# Telemetry_868Mhz.net
KiCad netlist of a schematic drawn in Altium Designer
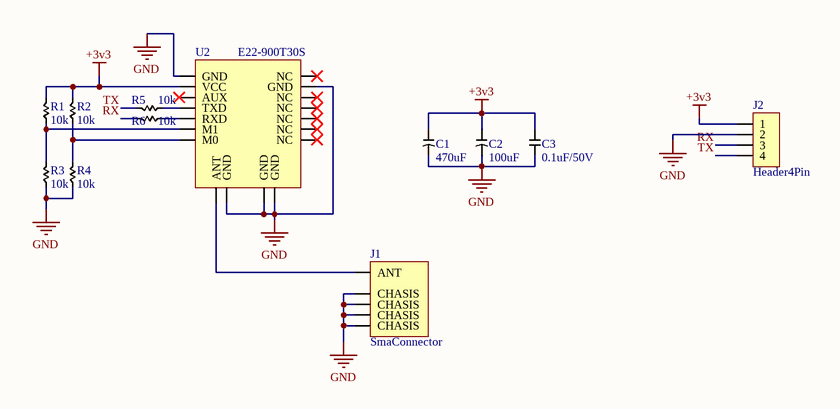
[diagram p0: Telemetry_868Mhz.SchDoc]

(export (version "E")
  (design (tool "Eeschema 10.0.6"))
  (components
    (comp (ref "C1")
      (value "470uF")
      (footprint "PKLH-016V471MG125-T/A5.0")
      (description "CAP.EL.470uF 16V 10x12.5 5MM 105C L.ESR 3000H TB K")
      (libsource (lib "Roket_Library") (part "PKLH-016V471MG125-T/A5.0"))
    )
    (comp (ref "C2")
      (value "100uF")
      (footprint "PKRM-035V101ME110-T/A5.0")
      (description "CAP.EL.100uF 50V 10x10 105C TH")
      (libsource (lib "Roket_Library") (part "PKRM-035V101ME110-T/A5.0"))
    )
    (comp (ref "C3")
      (value "0.1uF/50V")
      (footprint "Cap_0805")
      (description "MLCC (2012) 0805 100nF 50VDC ±5% X7R")
      (libsource (lib "Roket_Library") (part "CL21B104JBCNNNC"))
    )
    (comp (ref "J1")
      (value "SmaConnector")
      (footprint "RightAngled_SMA_Connector")
      (description "RP-SMA Connector Receptacle, Male Pin 50Ohm Through Hole, Right Angle Solder")
      (libsource (lib "Roket_Library") (part "L-KLS1-SMA002-B"))
    )
    (comp (ref "J2")
      (value "Header4Pin")
      (footprint "Header_4pin_Female")
      (description "PIN HEADER 4PIN(1x4) 2.54mm THT V/T")
      (libsource (lib "Roket_Library") (part "Header_4Pin"))
    )
    (comp (ref "R1")
      (value "10k")
      (footprint "RES_0805")
      (description "RES.(2012) 0805 10K Ohms 5% 1/8W-S 100PPM")
      (libsource (lib "Roket_Library") (part "0805S8J0103T5E"))
    )
    (comp (ref "R2")
      (value "10k")
      (footprint "RES_0805")
      (description "RES.(2012) 0805 10K Ohms 5% 1/8W-S 100PPM")
      (libsource (lib "Roket_Library") (part "0805S8J0103T5E"))
    )
    (comp (ref "R3")
      (value "10k")
      (footprint "RES_0805")
      (description "RES.(2012) 0805 10K Ohms 5% 1/8W-S 100PPM")
      (libsource (lib "Roket_Library") (part "0805S8J0103T5E"))
    )
    (comp (ref "R4")
      (value "10k")
      (footprint "RES_0805")
      (description "RES.(2012) 0805 10K Ohms 5% 1/8W-S 100PPM")
      (libsource (lib "Roket_Library") (part "0805S8J0103T5E"))
    )
    (comp (ref "R5")
      (value "10k")
      (footprint "RES_0805")
      (description "RES.(2012) 0805 10K Ohms 5% 1/8W-S 100PPM")
      (libsource (lib "Roket_Library") (part "0805S8J0103T5E"))
    )
    (comp (ref "R6")
      (value "10k")
      (footprint "RES_0805")
      (description "RES.(2012) 0805 10K Ohms 5% 1/8W-S 100PPM")
      (libsource (lib "Roket_Library") (part "0805S8J0103T5E"))
    )
    (comp (ref "U2")
      (value "E22-900T30S")
      (footprint "E22-900T30S")
      (description "LoRa, 868MHz 1W SMD long range, 5V Supply,RF Transmission 30 dBm, 10 k")
      (libsource (lib "Roket_Library") (part "E22-900T30S"))
    )
  )
  (nets
    (net (code "1") (name "+3v3") (class "Default")
      (node (ref "C1") (pin "1") (pinfunction "1_1") (pintype "passive"))
      (node (ref "C2") (pin "1") (pinfunction "1_1") (pintype "passive"))
      (node (ref "C3") (pin "1") (pinfunction "1_1") (pintype "passive"))
      (node (ref "J2") (pin "1") (pinfunction "1_1") (pintype "passive"))
      (node (ref "R1") (pin "2") (pinfunction "2_2") (pintype "passive"))
      (node (ref "R2") (pin "2") (pinfunction "2_2") (pintype "passive"))
      (node (ref "U2") (pin "6") (pinfunction "VCC_6") (pintype "passive"))
    )
    (net (code "2") (name "/RX") (class "Default")
      (node (ref "J2") (pin "3") (pinfunction "3_3") (pintype "passive"))
      (node (ref "R6") (pin "2") (pinfunction "2_2") (pintype "passive"))
    )
    (net (code "3") (name "/TX") (class "Default")
      (node (ref "J2") (pin "4") (pinfunction "4_4") (pintype "passive"))
      (node (ref "R5") (pin "2") (pinfunction "2_2") (pintype "passive"))
    )
    (net (code "4") (name "GND") (class "Default")
      (node (ref "C1") (pin "2") (pinfunction "2_2") (pintype "passive"))
      (node (ref "C2") (pin "2") (pinfunction "2_2") (pintype "passive"))
      (node (ref "C3") (pin "2") (pinfunction "2_2") (pintype "passive"))
      (node (ref "J1") (pin "2") (pinfunction "CHASIS_2") (pintype "passive"))
      (node (ref "J1") (pin "3") (pinfunction "CHASIS_3") (pintype "passive"))
      (node (ref "J1") (pin "4") (pinfunction "CHASIS_4") (pintype "passive"))
      (node (ref "J1") (pin "5") (pinfunction "CHASIS_5") (pintype "passive"))
      (node (ref "J2") (pin "2") (pinfunction "2_2") (pintype "passive"))
      (node (ref "R3") (pin "1") (pinfunction "1_1") (pintype "passive"))
      (node (ref "R4") (pin "1") (pinfunction "1_1") (pintype "passive"))
      (node (ref "U2") (pin "15") (pinfunction "GND_15") (pintype "passive"))
      (node (ref "U2") (pin "16") (pinfunction "GND_16") (pintype "passive"))
      (node (ref "U2") (pin "17") (pinfunction "GND_17") (pintype "passive"))
      (node (ref "U2") (pin "7") (pinfunction "GND_7") (pintype "passive"))
      (node (ref "U2") (pin "9") (pinfunction "GND_9") (pintype "passive"))
    )
    (net (code "5") (name "Net-(J1-ANT)") (class "Default")
      (node (ref "J1") (pin "1") (pinfunction "ANT_1") (pintype "passive"))
      (node (ref "U2") (pin "18") (pinfunction "ANT_18") (pintype "passive"))
    )
    (net (code "6") (name "Net-(U2-M0)") (class "Default")
      (node (ref "R2") (pin "1") (pinfunction "1_1") (pintype "passive"))
      (node (ref "R4") (pin "2") (pinfunction "2_2") (pintype "passive"))
      (node (ref "U2") (pin "1") (pinfunction "M0_1") (pintype "passive"))
    )
    (net (code "7") (name "Net-(U2-M1)") (class "Default")
      (node (ref "R1") (pin "1") (pinfunction "1_1") (pintype "passive"))
      (node (ref "R3") (pin "2") (pinfunction "2_2") (pintype "passive"))
      (node (ref "U2") (pin "2") (pinfunction "M1_2") (pintype "passive"))
    )
    (net (code "8") (name "Net-(U2-RXD)") (class "Default")
      (node (ref "R6") (pin "1") (pinfunction "1_1") (pintype "passive"))
      (node (ref "U2") (pin "3") (pinfunction "RXD_3") (pintype "passive"))
    )
    (net (code "9") (name "Net-(U2-TXD)") (class "Default")
      (node (ref "R5") (pin "1") (pinfunction "1_1") (pintype "passive"))
      (node (ref "U2") (pin "4") (pinfunction "TXD_4") (pintype "passive"))
    )
    (net (code "10") (name "unconnected-(U2-AUX-Pad5)") (class "Default")
      (node (ref "U2") (pin "5") (pinfunction "AUX_5") (pintype "passive+no_connect"))
    )
    (net (code "11") (name "unconnected-(U2-NC-Pad8)") (class "Default")
      (node (ref "U2") (pin "8") (pinfunction "NC_8") (pintype "passive+no_connect"))
    )
    (net (code "12") (name "unconnected-(U2-NC-Pad10)") (class "Default")
      (node (ref "U2") (pin "10") (pinfunction "NC_10") (pintype "passive+no_connect"))
    )
    (net (code "13") (name "unconnected-(U2-NC-Pad11)") (class "Default")
      (node (ref "U2") (pin "11") (pinfunction "NC_11") (pintype "passive+no_connect"))
    )
    (net (code "14") (name "unconnected-(U2-NC-Pad12)") (class "Default")
      (node (ref "U2") (pin "12") (pinfunction "NC_12") (pintype "passive+no_connect"))
    )
    (net (code "15") (name "unconnected-(U2-NC-Pad13)") (class "Default")
      (node (ref "U2") (pin "13") (pinfunction "NC_13") (pintype "passive+no_connect"))
    )
    (net (code "16") (name "unconnected-(U2-NC-Pad14)") (class "Default")
      (node (ref "U2") (pin "14") (pinfunction "NC_14") (pintype "passive+no_connect"))
    )
  )
)
